# PG15__Fuel_Gauge.net
KiCad netlist of a schematic drawn in Altium Designer
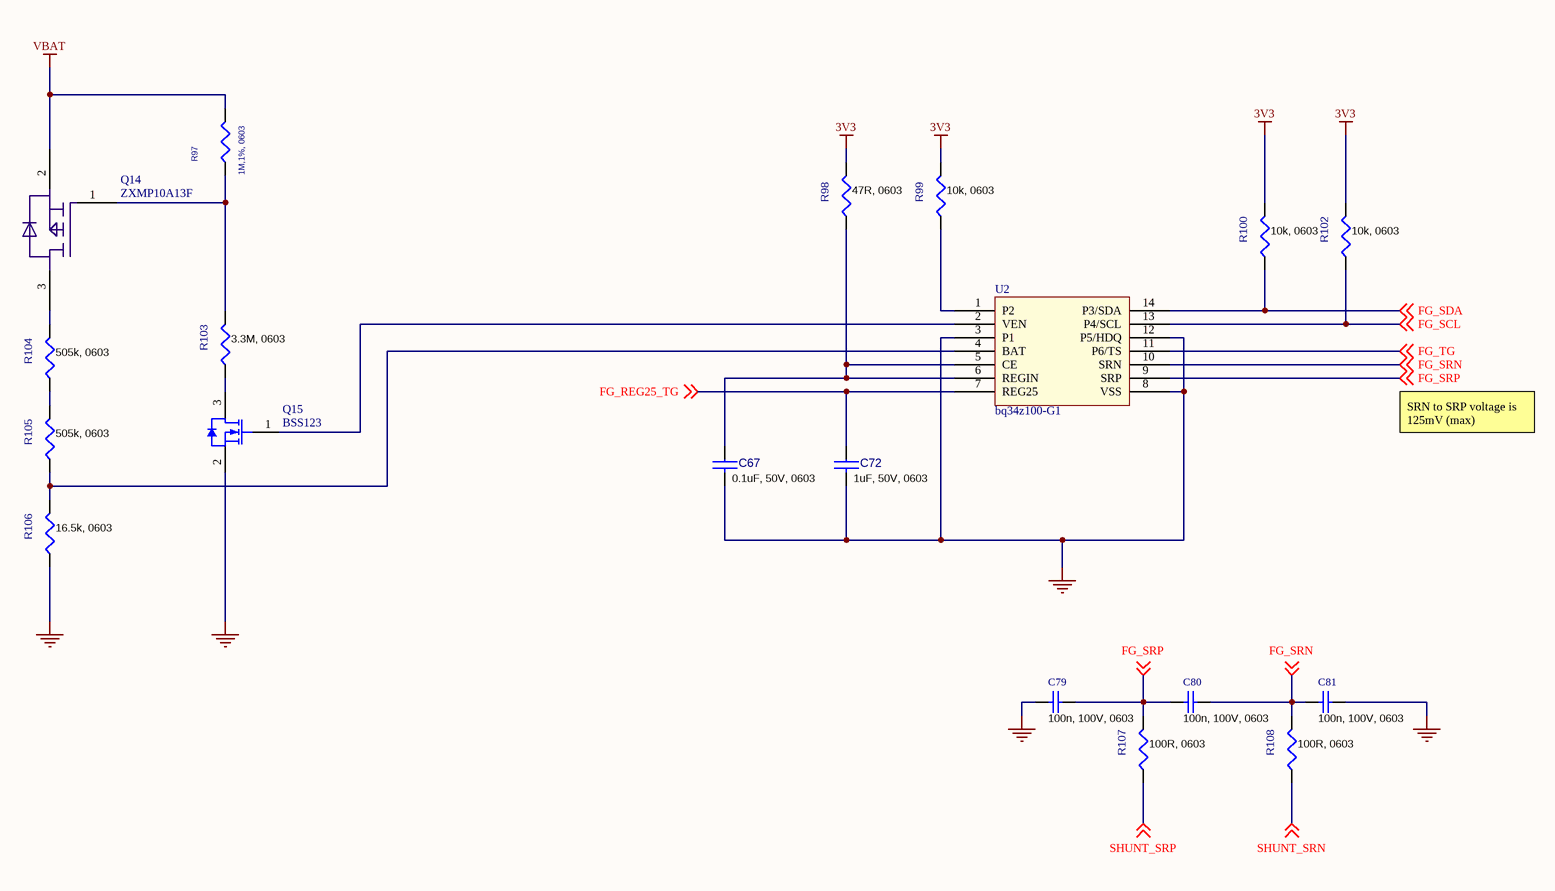
[diagram p0: PG15_ Fuel Gauge.SchDoc]

(export (version "E")
  (design (tool "Eeschema 10.0.6"))
  (components
    (comp (ref "C67")
      (value "0.1uF, 50V, 0603")
      (footprint "C0603")
      (description "CAP CER 0.1UF 50V 10% X7R 0603")
      (fields
        (field (name "MANUFACTURER") "Murata")
        (field (name "MANUFACTURER PART NUMBER") "GCJ188R71E104KA12D")
      )
      (libsource (lib "*") (part "CAP-Generic-0603"))
    )
    (comp (ref "C72")
      (value "1uF, 50V, 0603")
      (footprint "C0603")
      (description "CAP CER 1UF 50V 10% X7R 0603")
      (libsource (lib "*") (part "CAP-Generic-0603"))
    )
    (comp (ref "C79")
      (value "100n, 100V, 0603")
      (footprint "C0603")
      (description "CAP CER 100n 100V X7R 0603")
      (fields
        (field (name "MANUFACTURER") "Murata")
        (field (name "MANUFACTURER PART NUMBER") "GCJ188R72A104KA01D")
      )
      (libsource (lib "Miscellaneous Devices") (part "Cap"))
    )
    (comp (ref "C80")
      (value "100n, 100V, 0603")
      (footprint "C0603")
      (description "CAP CER 100n 100V X7R 0603")
      (fields
        (field (name "MANUFACTURER") "Murata")
        (field (name "MANUFACTURER PART NUMBER") "GCJ188R72A104KA01D")
      )
      (libsource (lib "Miscellaneous Devices") (part "Cap"))
    )
    (comp (ref "C81")
      (value "100n, 100V, 0603")
      (footprint "C0603")
      (description "CAP CER 100n 100V X7R 0603")
      (fields
        (field (name "MANUFACTURER") "Murata")
        (field (name "MANUFACTURER PART NUMBER") "GCJ188R72A104KA01D")
      )
      (libsource (lib "Miscellaneous Devices") (part "Cap"))
    )
    (comp (ref "Q14")
      (value "ZXMP10A13F")
      (footprint "SOT90P240X110-3N - ZXMP10A13F")
      (description "100V P-CHANNEL ENHANCEMENT MODE MOSFET")
      (libsource (lib "Altium") (part "ZXMP10A13F"))
    )
    (comp (ref "Q15")
      (value "BSS123")
      (footprint "FAIR-SOT23-3_V")
      (fields (field (name "MANUFACTURER") "Fairchild"))
      (libsource (lib "Altium Content Vault") (part "NEMOS-GSD-3"))
    )
    (comp (ref "R97")
      (value "1M,1%, 0603")
      (footprint "R0603")
      (libsource (lib "M2_V8_BMU_V1.0") (part "R-Generic-0603"))
    )
    (comp (ref "R98")
      (value "47R, 0603")
      (footprint "R0603")
      (description "RES SMD 47R OHM 1% 1/10W 0603")
      (libsource (lib "*") (part "R-Generic-0603"))
    )
    (comp (ref "R99")
      (value "10k, 0603")
      (footprint "R0603")
      (description "RES SMD 10k OHM 1% 1/10W 0603")
      (libsource (lib "*") (part "R-Generic-0603"))
    )
    (comp (ref "R100")
      (value "10k, 0603")
      (footprint "R0603")
      (description "RES SMD 10k OHM 1% 1/10W 0603")
      (libsource (lib "*") (part "R-Generic-0603"))
    )
    (comp (ref "R102")
      (value "10k, 0603")
      (footprint "R0603")
      (description "RES SMD 10k OHM 1% 1/10W 0603")
      (libsource (lib "*") (part "R-Generic-0603"))
    )
    (comp (ref "R103")
      (value "3.3M, 0603")
      (footprint "R0603")
      (description "RES SMD 3.3M OHM 1% 1/10W 0603")
      (libsource (lib "*") (part "R-Generic-0603"))
    )
    (comp (ref "R104")
      (value "505k, 0603")
      (footprint "R0603")
      (description "RES SMD 505k OHM 1% 1/10W 0603")
      (libsource (lib "*") (part "R-Generic-0603"))
    )
    (comp (ref "R105")
      (value "505k, 0603")
      (footprint "R0603")
      (description "RES SMD 505k OHM 1% 1/10W 0603")
      (libsource (lib "*") (part "R-Generic-0603"))
    )
    (comp (ref "R106")
      (value "16.5k, 0603")
      (footprint "R0603")
      (description "RES SMD 16.5k OHM 1% 1/10W 0603")
      (libsource (lib "*") (part "R-Generic-0603"))
    )
    (comp (ref "R107")
      (value "100R, 0603")
      (footprint "R0603")
      (description "RES SMD 100R OHM 1% 1/10W 0603")
      (libsource (lib "*") (part "R-Generic-0603"))
    )
    (comp (ref "R108")
      (value "100R, 0603")
      (footprint "R0603")
      (description "RES SMD 100R OHM 1% 1/10W 0603")
      (libsource (lib "*") (part "R-Generic-0603"))
    )
    (comp (ref "U2")
      (value "bq34z100-G1")
      (footprint "PW14")
      (description "Wide Range Fuel Gauge with Impedance Track™ Technology")
      (libsource (lib "Altium") (part "bq34z100-G1"))
    )
  )
  (nets
    (net (code "1") (name "3V3") (class "Default")
      (node (ref "R100") (pin "2") (pinfunction "2_2") (pintype "passive"))
      (node (ref "R102") (pin "2") (pinfunction "2_2") (pintype "passive"))
      (node (ref "R98") (pin "2") (pinfunction "2_2") (pintype "passive"))
      (node (ref "R99") (pin "2") (pinfunction "2_2") (pintype "passive"))
    )
    (net (code "2") (name "FG_REG25_TG") (class "Default")
      (node (ref "C72") (pin "1") (pinfunction "1_1") (pintype "passive"))
      (node (ref "U2") (pin "7") (pinfunction "REG25_7") (pintype "passive"))
    )
    (net (code "3") (name "FG_SCL") (class "Default")
      (node (ref "R102") (pin "1") (pinfunction "1_1") (pintype "passive"))
      (node (ref "U2") (pin "13") (pinfunction "P4/SCL_13") (pintype "passive"))
    )
    (net (code "4") (name "FG_SDA") (class "Default")
      (node (ref "R100") (pin "1") (pinfunction "1_1") (pintype "passive"))
      (node (ref "U2") (pin "14") (pinfunction "P3/SDA_14") (pintype "passive"))
    )
    (net (code "5") (name "FG_SRN") (class "Default")
      (node (ref "C80") (pin "1") (pinfunction "1_1") (pintype "passive"))
      (node (ref "C81") (pin "2") (pinfunction "2_2") (pintype "passive"))
      (node (ref "R108") (pin "2") (pinfunction "2_2") (pintype "passive"))
      (node (ref "U2") (pin "10") (pinfunction "SRN_10") (pintype "passive"))
    )
    (net (code "6") (name "FG_SRP") (class "Default")
      (node (ref "C79") (pin "1") (pinfunction "1_1") (pintype "passive"))
      (node (ref "C80") (pin "2") (pinfunction "2_2") (pintype "passive"))
      (node (ref "R107") (pin "2") (pinfunction "2_2") (pintype "passive"))
      (node (ref "U2") (pin "9") (pinfunction "SRP_9") (pintype "passive"))
    )
    (net (code "7") (name "FG_TG") (class "Default")
      (node (ref "U2") (pin "11") (pinfunction "P6/TS_11") (pintype "passive"))
    )
    (net (code "8") (name "GND") (class "Default")
      (node (ref "C67") (pin "2") (pinfunction "2_2") (pintype "passive"))
      (node (ref "C72") (pin "2") (pinfunction "2_2") (pintype "passive"))
      (node (ref "C79") (pin "2") (pinfunction "2_2") (pintype "passive"))
      (node (ref "C81") (pin "1") (pinfunction "1_1") (pintype "passive"))
      (node (ref "Q15") (pin "2") (pinfunction "S_2") (pintype "passive"))
      (node (ref "R106") (pin "1") (pinfunction "1_1") (pintype "passive"))
      (node (ref "U2") (pin "12") (pinfunction "P5/HDQ_12") (pintype "passive"))
      (node (ref "U2") (pin "3") (pinfunction "P1_3") (pintype "passive"))
      (node (ref "U2") (pin "8") (pinfunction "VSS_8") (pintype "passive"))
    )
    (net (code "9") (name "Net-(Q14-D)") (class "Default")
      (node (ref "Q14") (pin "3") (pinfunction "D_3") (pintype "passive"))
      (node (ref "R104") (pin "2") (pinfunction "2_2") (pintype "passive"))
    )
    (net (code "10") (name "Net-(Q14-G)") (class "Default")
      (node (ref "Q14") (pin "1") (pinfunction "G_1") (pintype "passive"))
      (node (ref "R103") (pin "2") (pinfunction "2_2") (pintype "passive"))
      (node (ref "R97") (pin "1") (pinfunction "1_1") (pintype "passive"))
    )
    (net (code "11") (name "Net-(Q15-D)") (class "Default")
      (node (ref "Q15") (pin "3") (pinfunction "D_3") (pintype "passive"))
      (node (ref "R103") (pin "1") (pinfunction "1_1") (pintype "passive"))
    )
    (net (code "12") (name "Net-(Q15-G)") (class "Default")
      (node (ref "Q15") (pin "1") (pinfunction "G_1") (pintype "passive"))
      (node (ref "U2") (pin "2") (pinfunction "VEN_2") (pintype "passive"))
    )
    (net (code "13") (name "Net-(R104-Pad1)") (class "Default")
      (node (ref "R104") (pin "1") (pinfunction "1_1") (pintype "passive"))
      (node (ref "R105") (pin "2") (pinfunction "2_2") (pintype "passive"))
    )
    (net (code "14") (name "Net-(U2-BAT)") (class "Default")
      (node (ref "R105") (pin "1") (pinfunction "1_1") (pintype "passive"))
      (node (ref "R106") (pin "2") (pinfunction "2_2") (pintype "passive"))
      (node (ref "U2") (pin "4") (pinfunction "BAT_4") (pintype "passive"))
    )
    (net (code "15") (name "Net-(U2-CE)") (class "Default")
      (node (ref "C67") (pin "1") (pinfunction "1_1") (pintype "passive"))
      (node (ref "R98") (pin "1") (pinfunction "1_1") (pintype "passive"))
      (node (ref "U2") (pin "5") (pinfunction "CE_5") (pintype "passive"))
      (node (ref "U2") (pin "6") (pinfunction "REGIN_6") (pintype "passive"))
    )
    (net (code "16") (name "Net-(U2-P2)") (class "Default")
      (node (ref "R99") (pin "1") (pinfunction "1_1") (pintype "passive"))
      (node (ref "U2") (pin "1") (pinfunction "P2_1") (pintype "passive"))
    )
    (net (code "17") (name "SHUNT_SRN") (class "Default")
      (node (ref "R108") (pin "1") (pinfunction "1_1") (pintype "passive"))
    )
    (net (code "18") (name "SHUNT_SRP") (class "Default")
      (node (ref "R107") (pin "1") (pinfunction "1_1") (pintype "passive"))
    )
    (net (code "19") (name "VBAT") (class "Default")
      (node (ref "Q14") (pin "2") (pinfunction "S_2") (pintype "passive"))
      (node (ref "R97") (pin "2") (pinfunction "2_2") (pintype "passive"))
    )
  )
)
